# LMP91000.net
KiCad netlist of a schematic drawn in EAGLE
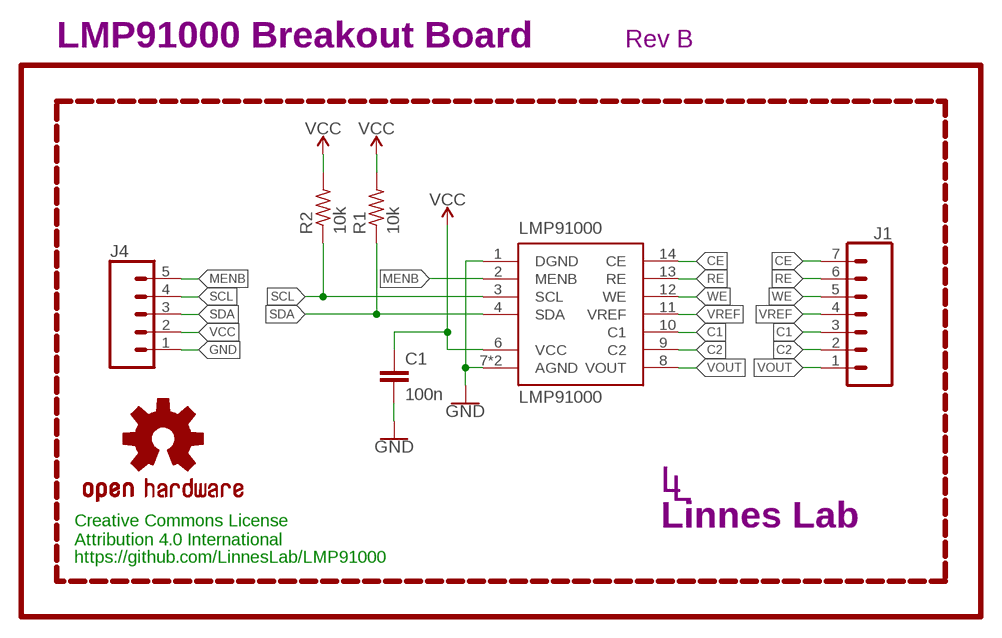
[diagram p0: schematic, sheet 1]

(export (version "E")
  (design (tool "Eeschema 10.0.6"))
  (components
    (comp (ref "C1")
      (value "100n")
      (footprint "eagle-import:C0402")
      (libsource (lib "eagle-import") (part "CAPACITOR0402"))
    )
    (comp (ref "J1")
      (value "CONN_07NO_SILK")
      (footprint "eagle-import:1X07_NO_SILK")
      (libsource (lib "eagle-import") (part "CONN_07NO_SILK"))
    )
    (comp (ref "J4")
      (value "CONN_05NO_SILK")
      (footprint "eagle-import:1X05_NO_SILK")
      (libsource (lib "eagle-import") (part "CONN_05NO_SILK"))
    )
    (comp (ref "LMP91000")
      (value "LMP91000")
      (footprint "eagle-import:WSON-14")
      (libsource (lib "eagle-import") (part "LMP91000"))
    )
    (comp (ref "LOGO1")
      (value "OSHW-LOGOS")
      (footprint "eagle-import:OSHW-LOGO-S")
      (libsource (lib "eagle-import") (part "OSHW-LOGOS"))
    )
    (comp (ref "R1")
      (value "10k")
      (footprint "eagle-import:R0402-BIGGER")
      (libsource (lib "eagle-import") (part "RESISTOR0402-BIGGER"))
    )
    (comp (ref "R2")
      (value "10k")
      (footprint "eagle-import:R0402-BIGGER")
      (libsource (lib "eagle-import") (part "RESISTOR0402-BIGGER"))
    )
    (comp (ref "U$1")
      (value "LINNES.LAB.05")
      (footprint "eagle-import:LINNES.LAB.05")
      (libsource (lib "eagle-import") (part "LINNES.LAB.05"))
    )
    (comp (ref "U$2")
      (value "LINNES.LAB.LOGO")
      (footprint "eagle-import:LINNES.LAB.LOGO")
      (libsource (lib "eagle-import") (part "LinnesLab-Logos_LINNES.LAB.LOGO"))
    )
    (comp (ref "U$3")
      (value "REVISION.B")
      (footprint "eagle-import:REV.B")
      (libsource (lib "eagle-import") (part "REVISION.B"))
    )
  )
  (nets
    (net (code "1") (name "C1") (class "Default")
      (node (ref "J1") (pin "3") (pinfunction "3_3") (pintype "passive"))
      (node (ref "LMP91000") (pin "10") (pinfunction "C1_10") (pintype "bidirectional"))
    )
    (net (code "2") (name "C2") (class "Default")
      (node (ref "J1") (pin "2") (pinfunction "2_2") (pintype "passive"))
      (node (ref "LMP91000") (pin "9") (pinfunction "C2_9") (pintype "bidirectional"))
    )
    (net (code "3") (name "CE") (class "Default")
      (node (ref "J1") (pin "7") (pinfunction "7_7") (pintype "passive"))
      (node (ref "LMP91000") (pin "14") (pinfunction "CE_14") (pintype "bidirectional"))
    )
    (net (code "4") (name "GND") (class "Default")
      (node (ref "C1") (pin "2") (pinfunction "2_2") (pintype "passive"))
      (node (ref "J4") (pin "1") (pinfunction "1_1") (pintype "passive"))
      (node (ref "LMP91000") (pin "1") (pinfunction "DGND_1") (pintype "bidirectional"))
      (node (ref "LMP91000") (pin "7") (pinfunction "AGND_7") (pintype "bidirectional"))
      (node (ref "LMP91000") (pin "DAP") (pinfunction "AGND_DAP") (pintype "bidirectional"))
    )
    (net (code "5") (name "MENB") (class "Default")
      (node (ref "J4") (pin "5") (pinfunction "5_5") (pintype "passive"))
      (node (ref "LMP91000") (pin "2") (pinfunction "MENB_2") (pintype "bidirectional"))
    )
    (net (code "6") (name "RE") (class "Default")
      (node (ref "J1") (pin "6") (pinfunction "6_6") (pintype "passive"))
      (node (ref "LMP91000") (pin "13") (pinfunction "RE_13") (pintype "bidirectional"))
    )
    (net (code "7") (name "SCL") (class "Default")
      (node (ref "J4") (pin "4") (pinfunction "4_4") (pintype "passive"))
      (node (ref "LMP91000") (pin "3") (pinfunction "SCL_3") (pintype "bidirectional"))
      (node (ref "R2") (pin "1") (pinfunction "1_1") (pintype "passive"))
    )
    (net (code "8") (name "SDA") (class "Default")
      (node (ref "J4") (pin "3") (pinfunction "3_3") (pintype "passive"))
      (node (ref "LMP91000") (pin "4") (pinfunction "SDA_4") (pintype "bidirectional"))
      (node (ref "R1") (pin "1") (pinfunction "1_1") (pintype "passive"))
    )
    (net (code "9") (name "VCC") (class "Default")
      (node (ref "C1") (pin "1") (pinfunction "1_1") (pintype "passive"))
      (node (ref "J4") (pin "2") (pinfunction "2_2") (pintype "passive"))
      (node (ref "LMP91000") (pin "6") (pinfunction "VCC_6") (pintype "bidirectional"))
      (node (ref "R1") (pin "2") (pinfunction "2_2") (pintype "passive"))
      (node (ref "R2") (pin "2") (pinfunction "2_2") (pintype "passive"))
    )
    (net (code "10") (name "VOUT") (class "Default")
      (node (ref "J1") (pin "1") (pinfunction "1_1") (pintype "passive"))
      (node (ref "LMP91000") (pin "8") (pinfunction "VOUT_8") (pintype "bidirectional"))
    )
    (net (code "11") (name "VREF") (class "Default")
      (node (ref "J1") (pin "4") (pinfunction "4_4") (pintype "passive"))
      (node (ref "LMP91000") (pin "11") (pinfunction "VREF_11") (pintype "bidirectional"))
    )
    (net (code "12") (name "WE") (class "Default")
      (node (ref "J1") (pin "5") (pinfunction "5_5") (pintype "passive"))
      (node (ref "LMP91000") (pin "12") (pinfunction "WE_12") (pintype "bidirectional"))
    )
  )
)
